# 190205_AVR-Control_V1_0.net
KiCad netlist of a schematic drawn in EAGLE
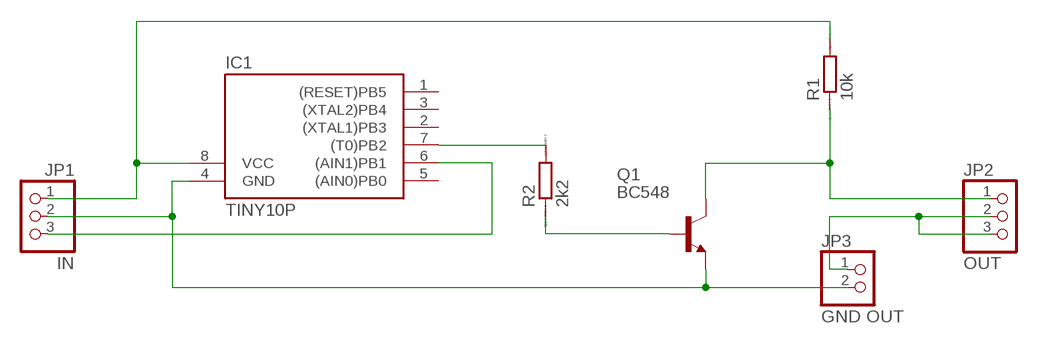
[diagram p0: schematic, sheet 1]

(export (version "E")
  (design (tool "Eeschema 10.0.6"))
  (components
    (comp (ref "IC1")
      (value "TINY10P")
      (footprint "eagle-import:DIL08")
      (libsource (lib "eagle-import") (part "TINY10P"))
    )
    (comp (ref "JP1")
      (value "IN")
      (footprint "eagle-import:1X03_90")
      (libsource (lib "eagle-import") (part "PINHD-1X3/90"))
    )
    (comp (ref "JP2")
      (value "OUT")
      (footprint "eagle-import:1X03_90")
      (libsource (lib "eagle-import") (part "PINHD-1X3/90"))
    )
    (comp (ref "JP3")
      (value "GND OUT")
      (footprint "eagle-import:1X02")
      (libsource (lib "eagle-import") (part "PINHD-1X2"))
    )
    (comp (ref "Q1")
      (value "BC548")
      (footprint "eagle-import:TO92-EBC")
      (libsource (lib "eagle-import") (part "BC548"))
    )
    (comp (ref "R1")
      (value "10k")
      (footprint "eagle-import:R1206")
      (libsource (lib "eagle-import") (part "RR1206"))
    )
    (comp (ref "R2")
      (value "2k2")
      (footprint "eagle-import:R1206")
      (libsource (lib "eagle-import") (part "RR1206"))
    )
  )
  (nets
    (net (code "1") (name "Net-(IC1-(AIN1)PB1)") (class "Default")
      (node (ref "IC1") (pin "6") (pinfunction "(AIN1)PB1_6") (pintype "bidirectional"))
      (node (ref "JP1") (pin "3") (pinfunction "3_3") (pintype "passive"))
    )
    (net (code "2") (name "Net-(IC1-(T0)PB2)") (class "Default")
      (node (ref "IC1") (pin "7") (pinfunction "(T0)PB2_7") (pintype "bidirectional"))
      (node (ref "R2") (pin "2") (pinfunction "2_2") (pintype "passive"))
    )
    (net (code "3") (name "Net-(IC1-GND)") (class "Default")
      (node (ref "IC1") (pin "4") (pinfunction "GND_4") (pintype "power_in"))
      (node (ref "JP1") (pin "2") (pinfunction "2_2") (pintype "passive"))
      (node (ref "JP3") (pin "2") (pinfunction "2_2") (pintype "passive"))
      (node (ref "Q1") (pin "E") (pinfunction "E_E") (pintype "passive"))
    )
    (net (code "4") (name "Net-(IC1-VCC)") (class "Default")
      (node (ref "IC1") (pin "8") (pinfunction "VCC_8") (pintype "power_in"))
      (node (ref "JP1") (pin "1") (pinfunction "1_1") (pintype "passive"))
      (node (ref "R1") (pin "2") (pinfunction "2_2") (pintype "passive"))
    )
    (net (code "5") (name "Net-(JP2-Pad1)") (class "Default")
      (node (ref "JP2") (pin "1") (pinfunction "1_1") (pintype "passive"))
      (node (ref "Q1") (pin "C") (pinfunction "C_C") (pintype "passive"))
      (node (ref "R1") (pin "1") (pinfunction "1_1") (pintype "passive"))
    )
    (net (code "6") (name "Net-(JP2-Pad2)") (class "Default")
      (node (ref "JP2") (pin "2") (pinfunction "2_2") (pintype "passive"))
      (node (ref "JP2") (pin "3") (pinfunction "3_3") (pintype "passive"))
      (node (ref "JP3") (pin "1") (pinfunction "1_1") (pintype "passive"))
    )
    (net (code "7") (name "Net-(Q1-PadB)") (class "Default")
      (node (ref "Q1") (pin "B") (pinfunction "B_B") (pintype "passive"))
      (node (ref "R2") (pin "1") (pinfunction "1_1") (pintype "passive"))
    )
    (net (code "8") (name "unconnected-(IC1-(AIN0)PB0-Pad5)") (class "Default")
      (node (ref "IC1") (pin "5") (pinfunction "(AIN0)PB0_5") (pintype "bidirectional"))
    )
    (net (code "9") (name "unconnected-(IC1-(RESET)PB5-Pad1)") (class "Default")
      (node (ref "IC1") (pin "1") (pinfunction "(RESET)PB5_1") (pintype "bidirectional"))
    )
    (net (code "10") (name "unconnected-(IC1-(XTAL1)PB3-Pad2)") (class "Default")
      (node (ref "IC1") (pin "2") (pinfunction "(XTAL1)PB3_2") (pintype "bidirectional"))
    )
    (net (code "11") (name "unconnected-(IC1-(XTAL2)PB4-Pad3)") (class "Default")
      (node (ref "IC1") (pin "3") (pinfunction "(XTAL2)PB4_3") (pintype "bidirectional"))
    )
  )
)
